# Microcontroller.net
KiCad netlist of a schematic drawn in Altium Designer
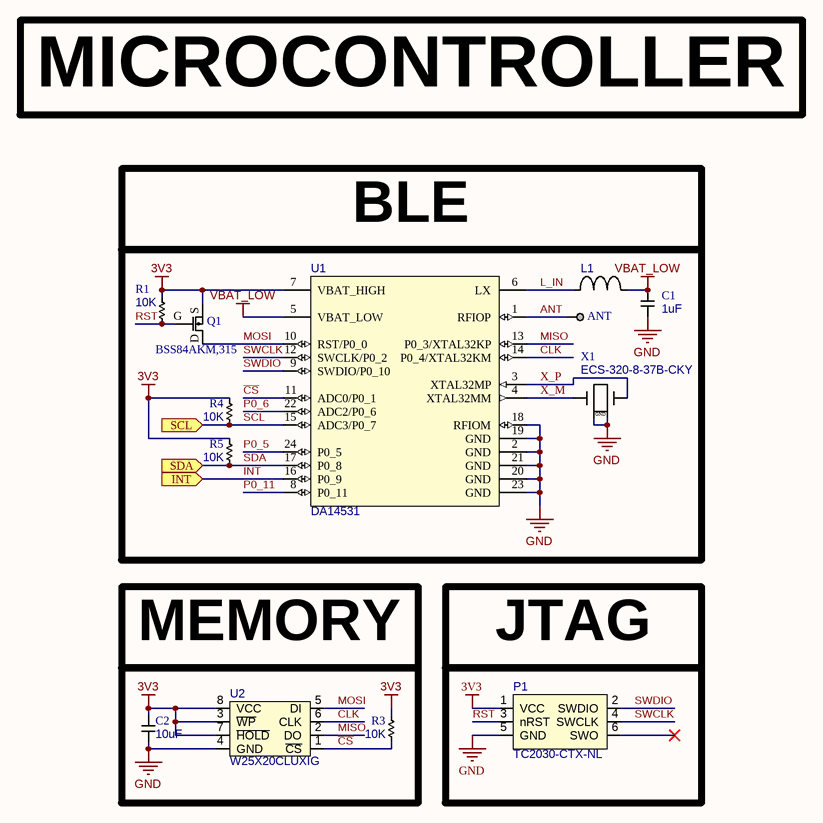
[diagram p0: Microcontroller.SchDoc]

(export (version "E")
  (design (tool "Eeschema 10.0.6"))
  (components
    (comp (ref "ANT")
      (value "0.1\" Header")
      (footprint "0.1\" Header")
      (libsource (lib "smLib") (part "0.1{dblquote} Header"))
    )
    (comp (ref "C1")
      (value "1uF")
      (footprint "CAP_0402_HIGH")
      (description "0402 Capacitor")
      (libsource (lib "smLib") (part "Capacitor_0402"))
    )
    (comp (ref "C2")
      (value "10uF")
      (footprint "CAP_0402_HIGH")
      (description "0402 Capacitor")
      (libsource (lib "smLib") (part "Capacitor_0402"))
    )
    (comp (ref "L1")
      (value "CIGT201610EH2R2MNE")
      (footprint "CIGT201610EH2R2MNE")
      (description "CIGT201610EH2R2MNE 2.2µH Unshielded Thin Film Inductor 2.5A 87mOhm Max 0806 (2016 Metric)")
      (libsource (lib "smLib") (part "CIGT201610EH2R2MNE"))
    )
    (comp (ref "P1")
      (value "TC2030-CTX-NL")
      (footprint "TC2030-CTX-NL")
      (description "TC2030-CTX-NL Tag Connect Cable")
      (libsource (lib "smLib") (part "TC2030-CTX-NL"))
    )
    (comp (ref "Q1")
      (value "BSS84AKM,315")
      (footprint "BSS84AKM,315")
      (description "BSS84AKM,315 MOSFET P-CH 50V SOT883")
      (libsource (lib "smLib") (part "BSS84AKM,315"))
    )
    (comp (ref "R1")
      (value "10K")
      (footprint "RES_0402_HIGH")
      (description "0402 Resistor")
      (libsource (lib "smLib") (part "Resistor_0402"))
    )
    (comp (ref "R3")
      (value "10K")
      (footprint "RES_0402_HIGH")
      (description "0402 Resistor")
      (libsource (lib "smLib") (part "Resistor_0402"))
    )
    (comp (ref "R4")
      (value "10K")
      (footprint "RES_0402_HIGH")
      (description "0402 Resistor")
      (libsource (lib "smLib") (part "Resistor_0402"))
    )
    (comp (ref "R5")
      (value "10K")
      (footprint "RES_0402_HIGH")
      (description "0402 Resistor")
      (libsource (lib "smLib") (part "Resistor_0402"))
    )
    (comp (ref "U1")
      (value "DA14531")
      (footprint "DA14531 QFN")
      (description "DA14531 IC RF TxRx + MCU Bluetooth Bluetooth v5.1 2.4GHz 24-WFQFN, FC")
      (libsource (lib "smLib") (part "DA14531 QFN"))
    )
    (comp (ref "U2")
      (value "W25X20CLUXIG")
      (footprint "W25X20CLUXIG")
      (description "W25X20CLUXIG FLASH Memory IC 2Mb (256K x 8) SPI 104MHz  8-USON (2x3)")
      (libsource (lib "smLib") (part "W25X20CLUXIG"))
    )
    (comp (ref "X1")
      (value "ECS-320-8-37B-CKY")
      (footprint "ECS-320-8-37B-CKY")
      (description "ECS-320-8-37B-CKY CRYSTAL 32.0000MHZ 8PF SMD")
      (libsource (lib "smLib") (part "ECS-320-8-37B-CKY"))
    )
  )
  (nets
    (net (code "1") (name "/ANT") (class "Default")
      (node (ref "ANT") (pin "1") (pinfunction "1_1") (pintype "passive"))
      (node (ref "U1") (pin "1") (pinfunction "RFIOP_1") (pintype "bidirectional"))
    )
    (net (code "2") (name "/CLK") (class "Default")
      (node (ref "U1") (pin "14") (pinfunction "P0_4/XTAL32KM_14") (pintype "bidirectional"))
      (node (ref "U2") (pin "6") (pinfunction "CLK_6") (pintype "passive"))
    )
    (net (code "3") (name "/INT") (class "Default")
      (node (ref "U1") (pin "16") (pinfunction "P0_9_16") (pintype "bidirectional"))
    )
    (net (code "4") (name "/L_IN") (class "Default")
      (node (ref "L1") (pin "1") (pinfunction "1_1") (pintype "passive"))
      (node (ref "U1") (pin "6") (pinfunction "LX_6") (pintype "passive"))
    )
    (net (code "5") (name "/MISO") (class "Default")
      (node (ref "U1") (pin "13") (pinfunction "P0_3/XTAL32KP_13") (pintype "bidirectional"))
      (node (ref "U2") (pin "2") (pinfunction "DO_2") (pintype "passive"))
    )
    (net (code "6") (name "/MOSI") (class "Default")
      (node (ref "Q1") (pin "D") (pinfunction "D_D") (pintype "passive"))
      (node (ref "U1") (pin "10") (pinfunction "RST/P0_0_10") (pintype "bidirectional"))
      (node (ref "U2") (pin "5") (pinfunction "DI_5") (pintype "passive"))
    )
    (net (code "7") (name "/P0_5") (class "Default")
      (node (ref "U1") (pin "24") (pinfunction "P0_5_24") (pintype "bidirectional"))
    )
    (net (code "8") (name "/P0_6") (class "Default")
      (node (ref "U1") (pin "22") (pinfunction "ADC2/P0_6_22") (pintype "bidirectional"))
    )
    (net (code "9") (name "/P0_11") (class "Default")
      (node (ref "U1") (pin "8") (pinfunction "P0_11_8") (pintype "bidirectional"))
    )
    (net (code "10") (name "/RST") (class "Default")
      (node (ref "P1") (pin "3") (pinfunction "nRST_3") (pintype "passive"))
      (node (ref "Q1") (pin "G") (pinfunction "G_G") (pintype "passive"))
      (node (ref "R1") (pin "1") (pinfunction "1_1") (pintype "passive"))
    )
    (net (code "11") (name "/SCL") (class "Default")
      (node (ref "R4") (pin "1") (pinfunction "1_1") (pintype "passive"))
      (node (ref "U1") (pin "15") (pinfunction "ADC3/P0_7_15") (pintype "bidirectional"))
    )
    (net (code "12") (name "/SDA") (class "Default")
      (node (ref "R5") (pin "1") (pinfunction "1_1") (pintype "passive"))
      (node (ref "U1") (pin "17") (pinfunction "P0_8_17") (pintype "bidirectional"))
    )
    (net (code "13") (name "/SWCLK") (class "Default")
      (node (ref "P1") (pin "4") (pinfunction "SWCLK_4") (pintype "passive"))
      (node (ref "U1") (pin "12") (pinfunction "SWCLK/P0_2_12") (pintype "bidirectional"))
    )
    (net (code "14") (name "/SWDIO") (class "Default")
      (node (ref "P1") (pin "2") (pinfunction "SWDIO_2") (pintype "passive"))
      (node (ref "U1") (pin "9") (pinfunction "SWDIO/P0_10_9") (pintype "bidirectional"))
    )
    (net (code "15") (name "/X_M") (class "Default")
      (node (ref "U1") (pin "4") (pinfunction "XTAL32MM_4") (pintype "output"))
      (node (ref "X1") (pin "1") (pinfunction "1_1") (pintype "passive"))
    )
    (net (code "16") (name "/X_P") (class "Default")
      (node (ref "U1") (pin "3") (pinfunction "XTAL32MP_3") (pintype "input"))
      (node (ref "X1") (pin "3") (pinfunction "3_3") (pintype "passive"))
    )
    (net (code "17") (name "/~{CS}") (class "Default")
      (node (ref "R3") (pin "1") (pinfunction "1_1") (pintype "passive"))
      (node (ref "U1") (pin "11") (pinfunction "ADC0/P0_1_11") (pintype "bidirectional"))
      (node (ref "U2") (pin "1") (pinfunction "~{CS}_1") (pintype "passive"))
    )
    (net (code "18") (name "3V3") (class "Default")
      (node (ref "C2") (pin "2") (pinfunction "2_2") (pintype "passive"))
      (node (ref "P1") (pin "1") (pinfunction "VCC_1") (pintype "passive"))
      (node (ref "Q1") (pin "S") (pinfunction "S_S") (pintype "passive"))
      (node (ref "R1") (pin "2") (pinfunction "2_2") (pintype "passive"))
      (node (ref "R3") (pin "2") (pinfunction "2_2") (pintype "passive"))
      (node (ref "R4") (pin "2") (pinfunction "2_2") (pintype "passive"))
      (node (ref "R5") (pin "2") (pinfunction "2_2") (pintype "passive"))
      (node (ref "U1") (pin "7") (pinfunction "VBAT_HIGH_7") (pintype "power_in"))
      (node (ref "U2") (pin "3") (pinfunction "~{WP}_3") (pintype "passive"))
      (node (ref "U2") (pin "7") (pinfunction "~{HOLD}_7") (pintype "passive"))
      (node (ref "U2") (pin "8") (pinfunction "VCC_8") (pintype "passive"))
    )
    (net (code "19") (name "GND") (class "Default")
      (node (ref "C1") (pin "1") (pinfunction "1_1") (pintype "passive"))
      (node (ref "C2") (pin "1") (pinfunction "1_1") (pintype "passive"))
      (node (ref "P1") (pin "5") (pinfunction "GND_5") (pintype "passive"))
      (node (ref "U1") (pin "18") (pinfunction "RFIOM_18") (pintype "bidirectional"))
      (node (ref "U1") (pin "19") (pinfunction "GND_19") (pintype "power_in"))
      (node (ref "U1") (pin "2") (pinfunction "GND_2") (pintype "power_in"))
      (node (ref "U1") (pin "20") (pinfunction "GND_20") (pintype "power_in"))
      (node (ref "U1") (pin "21") (pinfunction "GND_21") (pintype "power_in"))
      (node (ref "U1") (pin "23") (pinfunction "GND_23") (pintype "power_in"))
      (node (ref "U2") (pin "4") (pinfunction "GND_4") (pintype "passive"))
      (node (ref "X1") (pin "2") (pinfunction "2_2") (pintype "passive"))
      (node (ref "X1") (pin "4") (pinfunction "GND_4") (pintype "passive"))
    )
    (net (code "20") (name "VBAT_LOW") (class "Default")
      (node (ref "C1") (pin "2") (pinfunction "2_2") (pintype "passive"))
      (node (ref "L1") (pin "2") (pinfunction "2_2") (pintype "passive"))
      (node (ref "U1") (pin "5") (pinfunction "VBAT_LOW_5") (pintype "power_in"))
    )
    (net (code "21") (name "unconnected-(P1-SWO-Pad6)") (class "Default")
      (node (ref "P1") (pin "6") (pinfunction "SWO_6") (pintype "passive+no_connect"))
    )
  )
)
